# External_Power_Connectors.net
KiCad netlist of a schematic drawn in Altium Designer
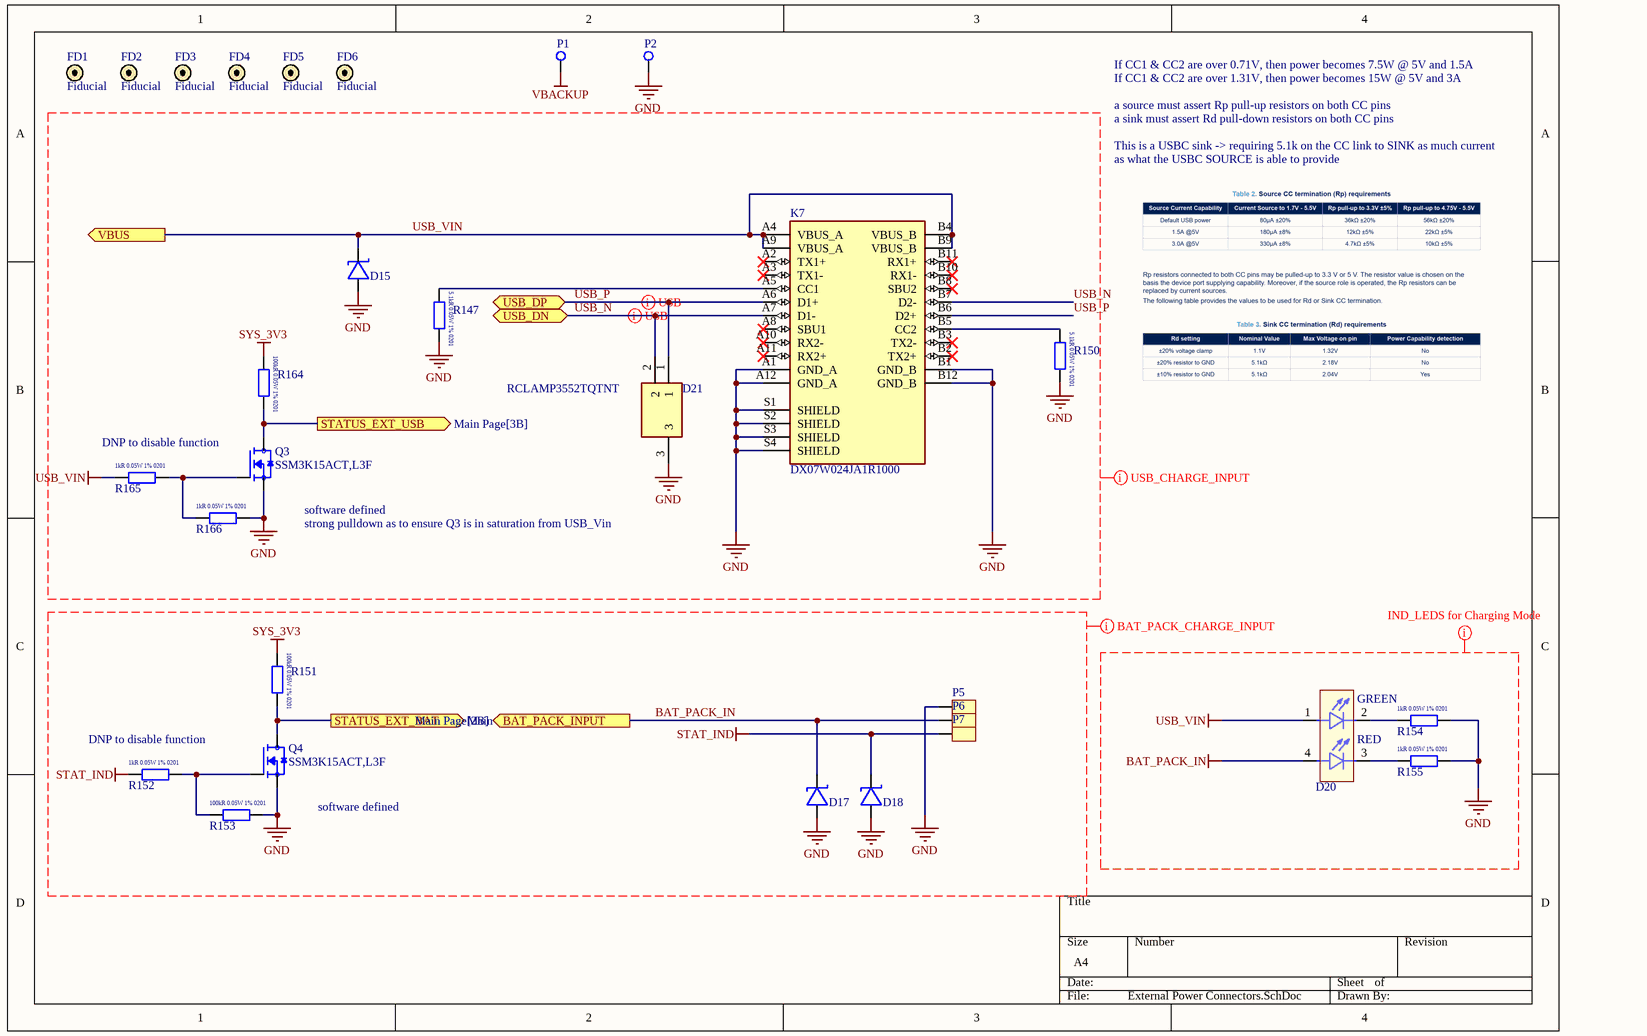
[diagram p0: External Power Connectors.SchDoc]

(export (version "E")
  (design (tool "Eeschema 10.0.6"))
  (components
    (comp (ref "D15")
      (value "RCLAMP04041PW.C")
      (footprint "RCLAMP04041PW.C")
      (description "8V Clamp 20A (8/20µs) Ipp Tvs Diode Surface Mount 2-DFN (1x0.6)")
      (libsource (lib "Gesturelink Schematic Library") (part "RCLAMP04041PW.C"))
    )
    (comp (ref "D17")
      (value "RCLAMP04041PW.C")
      (footprint "RCLAMP04041PW.C")
      (description "8V Clamp 20A (8/20µs) Ipp Tvs Diode Surface Mount 2-DFN (1x0.6)")
      (libsource (lib "Gesturelink Schematic Library") (part "RCLAMP04041PW.C"))
    )
    (comp (ref "D18")
      (value "RCLAMP04041PW.C")
      (footprint "RCLAMP04041PW.C")
      (description "8V Clamp 20A (8/20µs) Ipp Tvs Diode Surface Mount 2-DFN (1x0.6)")
      (libsource (lib "Gesturelink Schematic Library") (part "RCLAMP04041PW.C"))
    )
    (comp (ref "D20")
      (value "APGB0607G22R23C")
      (footprint "LED_APGB0607G22R23C")
      (description "Green, Red 525nm Green, 624nm Red LED Indication - Discrete 2.85V Green, 1.95V Red 4-SMD, No Lead")
      (libsource (lib "Gesturelink Schematic Library") (part "APGB0607G22R23C"))
    )
    (comp (ref "D21")
      (value "RCLAMP3552TQTNT")
      (footprint "SamacSys:RCLAMP3552TQTNT")
      (description "TVS Diode (Bi-directional)")
      (fields (field (name "MOUSER PART NUMBER") "947-RCLAMP3552TQTNT"))
      (libsource (lib "*") (part "RCLAMP3552TQTNT"))
    )
    (comp (ref "FD1")
      (value "Fiducial")
      (footprint "Fiducial")
      (libsource (lib "Gesturelink Schematic Library") (part "Fiducial"))
    )
    (comp (ref "FD2")
      (value "Fiducial")
      (footprint "Fiducial")
      (libsource (lib "Gesturelink Schematic Library") (part "Fiducial"))
    )
    (comp (ref "FD3")
      (value "Fiducial")
      (footprint "Fiducial")
      (libsource (lib "Gesturelink Schematic Library") (part "Fiducial"))
    )
    (comp (ref "FD4")
      (value "Fiducial")
      (footprint "Fiducial")
      (libsource (lib "Gesturelink Schematic Library") (part "Fiducial"))
    )
    (comp (ref "FD5")
      (value "Fiducial")
      (footprint "Fiducial")
      (libsource (lib "Gesturelink Schematic Library") (part "Fiducial"))
    )
    (comp (ref "FD6")
      (value "Fiducial")
      (footprint "Fiducial")
      (libsource (lib "Gesturelink Schematic Library") (part "Fiducial"))
    )
    (comp (ref "K7")
      (value "DX07W024JA1R1000")
      (footprint "JAE_DX07W024JA1R1000")
      (fields (field (name "MF") "JAE Electronics"))
      (libsource (lib "Gesturelink Schematic Library") (part "DX07W024JA1R1000"))
    )
    (comp (ref "P1")
      (value "Pogo pin Pad")
      (footprint "S70-220101045R")
      (description "Contact Spring Surface Mount")
      (libsource (lib "Gesturelink Schematic Library") (part "Pogo pin Pad"))
    )
    (comp (ref "P2")
      (value "Pogo pin Pad")
      (footprint "S70-220101045R")
      (description "Contact Spring Surface Mount")
      (libsource (lib "Gesturelink Schematic Library") (part "Pogo pin Pad"))
    )
    (comp (ref "P5")
      (value "Pad for Bat")
      (footprint "Pad for Bat")
      (libsource (lib "Gesturelink Schematic Library") (part "Pad for Bat"))
    )
    (comp (ref "P6")
      (value "Pad for Bat")
      (footprint "Pad for Bat")
      (libsource (lib "Gesturelink Schematic Library") (part "Pad for Bat"))
    )
    (comp (ref "P7")
      (value "Pad for Bat")
      (footprint "Pad for Bat")
      (libsource (lib "Gesturelink Schematic Library") (part "Pad for Bat"))
    )
    (comp (ref "Q3")
      (value "SSM3K15ACT,L3F")
      (footprint "SSM3K15ACT")
      (description "N-Channel 30 V 100mA (Ta) 100mW (Ta) Surface Mount CST3")
      (libsource (lib "Gesturelink Schematic Library") (part "SSM3K15ACT,L3F"))
    )
    (comp (ref "Q4")
      (value "SSM3K15ACT,L3F")
      (footprint "SSM3K15ACT")
      (description "N-Channel 30 V 100mA (Ta) 100mW (Ta) Surface Mount CST3")
      (libsource (lib "Gesturelink Schematic Library") (part "SSM3K15ACT,L3F"))
    )
    (comp (ref "R147")
      (value "ERJ-1GNF5101C")
      (footprint "RESC0603X03L")
      (description "5.1 kOhms ±1% 0.05W, 1/20W Chip Resistor 0201 (0603 Metric) Thick Film")
      (libsource (lib "Resistors") (part "ERJ-1GNF5101C"))
    )
    (comp (ref "R150")
      (value "ERJ-1GNF5101C")
      (footprint "RESC0603X03L")
      (description "5.1 kOhms ±1% 0.05W, 1/20W Chip Resistor 0201 (0603 Metric) Thick Film")
      (libsource (lib "Resistors") (part "ERJ-1GNF5101C"))
    )
    (comp (ref "R151")
      (value "ERJ-1GNF1003C")
      (footprint "RESC0603X03L")
      (description "100 kOhms ±1% 0.05W, 1/20W Chip Resistor 0201 (0603 Metric) Thick Film")
      (libsource (lib "Resistors") (part "ERJ-1GNF1003C"))
    )
    (comp (ref "R152")
      (value "ERJ-1GNF1001C")
      (footprint "RESC0603X03L")
      (description "1 kOhms ±1% 0.05W, 1/20W Chip Resistor 0201 (0603 Metric) Thick Film")
      (libsource (lib "Resistors") (part "ERJ-1GNF1001C"))
    )
    (comp (ref "R153")
      (value "ERJ-1GNF1003C")
      (footprint "RESC0603X03L")
      (description "100 kOhms ±1% 0.05W, 1/20W Chip Resistor 0201 (0603 Metric) Thick Film")
      (libsource (lib "") (part "ERJ-1GNF1003C_1"))
    )
    (comp (ref "R154")
      (value "ERJ-1GNF1001C")
      (footprint "RESC0603X03L")
      (description "1 kOhms ±1% 0.05W, 1/20W Chip Resistor 0201 (0603 Metric) Thick Film")
      (libsource (lib "Resistors") (part "ERJ-1GNF1001C"))
    )
    (comp (ref "R155")
      (value "ERJ-1GNF1001C")
      (footprint "RESC0603X03L")
      (description "1 kOhms ±1% 0.05W, 1/20W Chip Resistor 0201 (0603 Metric) Thick Film")
      (libsource (lib "Resistors") (part "ERJ-1GNF1001C"))
    )
    (comp (ref "R164")
      (value "ERJ-1GNF1003C")
      (footprint "RESC0603X03L")
      (description "100 kOhms ±1% 0.05W, 1/20W Chip Resistor 0201 (0603 Metric) Thick Film")
      (libsource (lib "Resistors") (part "ERJ-1GNF1003C"))
    )
    (comp (ref "R165")
      (value "ERJ-1GNF1001C")
      (footprint "RESC0603X03L")
      (description "1 kOhms ±1% 0.05W, 1/20W Chip Resistor 0201 (0603 Metric) Thick Film")
      (libsource (lib "Resistors") (part "ERJ-1GNF1001C"))
    )
    (comp (ref "R166")
      (value "ERJ-1GNF1001C")
      (footprint "RESC0603X03L")
      (description "1 kOhms ±1% 0.05W, 1/20W Chip Resistor 0201 (0603 Metric) Thick Film")
      (libsource (lib "Resistors") (part "ERJ-1GNF1001C"))
    )
  )
  (nets
    (net (code "1") (name "/STATUS_EXT_BAT") (class "Default")
      (node (ref "Q4") (pin "2") (pinfunction "D_2") (pintype "passive"))
      (node (ref "R151") (pin "2") (pinfunction "2_2") (pintype "passive"))
    )
    (net (code "2") (name "/STATUS_EXT_USB") (class "Default")
      (node (ref "Q3") (pin "2") (pinfunction "D_2") (pintype "passive"))
      (node (ref "R164") (pin "2") (pinfunction "2_2") (pintype "passive"))
    )
    (net (code "3") (name "/USB_N") (class "Default")
      (node (ref "D21") (pin "2") (pinfunction "2_2") (pintype "passive"))
      (node (ref "K7") (pin "A7") (pinfunction "D1-_A7") (pintype "bidirectional"))
      (node (ref "K7") (pin "B7") (pinfunction "D2-_B7") (pintype "bidirectional"))
    )
    (net (code "4") (name "/USB_P") (class "Default")
      (node (ref "D21") (pin "1") (pinfunction "1_1") (pintype "passive"))
      (node (ref "K7") (pin "A6") (pinfunction "D1+_A6") (pintype "bidirectional"))
      (node (ref "K7") (pin "B6") (pinfunction "D2+_B6") (pintype "bidirectional"))
    )
    (net (code "5") (name "BAT_PACK_IN") (class "Default")
      (node (ref "D17") (pin "2") (pinfunction "16_2") (pintype "passive"))
      (node (ref "D20") (pin "4") (pinfunction "A_RED_4") (pintype "passive"))
      (node (ref "P6") (pin "1") (pinfunction "1_1") (pintype "passive"))
    )
    (net (code "6") (name "GND") (class "Default")
      (node (ref "D15") (pin "1") (pinfunction "16_1") (pintype "passive"))
      (node (ref "D17") (pin "1") (pinfunction "16_1") (pintype "passive"))
      (node (ref "D18") (pin "1") (pinfunction "16_1") (pintype "passive"))
      (node (ref "D21") (pin "3") (pinfunction "3_3") (pintype "passive"))
      (node (ref "K7") (pin "A1") (pinfunction "GND_A_A1") (pintype "power_in"))
      (node (ref "K7") (pin "A12") (pinfunction "GND_A_A12") (pintype "power_in"))
      (node (ref "K7") (pin "B1") (pinfunction "GND_B_B1") (pintype "power_in"))
      (node (ref "K7") (pin "B12") (pinfunction "GND_B_B12") (pintype "power_in"))
      (node (ref "K7") (pin "S1") (pinfunction "SHIELD_S1") (pintype "passive"))
      (node (ref "K7") (pin "S2") (pinfunction "SHIELD_S2") (pintype "passive"))
      (node (ref "K7") (pin "S3") (pinfunction "SHIELD_S3") (pintype "passive"))
      (node (ref "K7") (pin "S4") (pinfunction "SHIELD_S4") (pintype "passive"))
      (node (ref "P2") (pin "1") (pinfunction "1_1") (pintype "passive"))
      (node (ref "P5") (pin "1") (pinfunction "1_1") (pintype "passive"))
      (node (ref "Q3") (pin "3") (pinfunction "S_3") (pintype "passive"))
      (node (ref "Q4") (pin "3") (pinfunction "S_3") (pintype "passive"))
      (node (ref "R147") (pin "2") (pinfunction "2_2") (pintype "passive"))
      (node (ref "R150") (pin "2") (pinfunction "2_2") (pintype "passive"))
      (node (ref "R153") (pin "2") (pinfunction "2_2") (pintype "passive"))
      (node (ref "R154") (pin "2") (pinfunction "2_2") (pintype "passive"))
      (node (ref "R155") (pin "2") (pinfunction "2_2") (pintype "passive"))
      (node (ref "R166") (pin "2") (pinfunction "2_2") (pintype "passive"))
    )
    (net (code "7") (name "Net-(D20-C_GREEN)") (class "Default")
      (node (ref "D20") (pin "2") (pinfunction "C_GREEN_2") (pintype "passive"))
      (node (ref "R154") (pin "1") (pinfunction "1_1") (pintype "passive"))
    )
    (net (code "8") (name "Net-(D20-C_RED)") (class "Default")
      (node (ref "D20") (pin "3") (pinfunction "C_RED_3") (pintype "passive"))
      (node (ref "R155") (pin "1") (pinfunction "1_1") (pintype "passive"))
    )
    (net (code "9") (name "Net-(K7-CC1)") (class "Default")
      (node (ref "K7") (pin "A5") (pinfunction "CC1_A5") (pintype "bidirectional"))
      (node (ref "R147") (pin "1") (pinfunction "1_1") (pintype "passive"))
    )
    (net (code "10") (name "Net-(K7-CC2)") (class "Default")
      (node (ref "K7") (pin "B5") (pinfunction "CC2_B5") (pintype "bidirectional"))
      (node (ref "R150") (pin "1") (pinfunction "1_1") (pintype "passive"))
    )
    (net (code "11") (name "Net-(Q3-G)") (class "Default")
      (node (ref "Q3") (pin "1") (pinfunction "G_1") (pintype "passive"))
      (node (ref "R165") (pin "2") (pinfunction "2_2") (pintype "passive"))
      (node (ref "R166") (pin "1") (pinfunction "1_1") (pintype "passive"))
    )
    (net (code "12") (name "Net-(Q4-G)") (class "Default")
      (node (ref "Q4") (pin "1") (pinfunction "G_1") (pintype "passive"))
      (node (ref "R152") (pin "2") (pinfunction "2_2") (pintype "passive"))
      (node (ref "R153") (pin "1") (pinfunction "1_1") (pintype "passive"))
    )
    (net (code "13") (name "STAT_IND") (class "Default")
      (node (ref "D18") (pin "2") (pinfunction "16_2") (pintype "passive"))
      (node (ref "P7") (pin "1") (pinfunction "1_1") (pintype "passive"))
      (node (ref "R152") (pin "1") (pinfunction "1_1") (pintype "passive"))
    )
    (net (code "14") (name "SYS_3V3") (class "Default")
      (node (ref "R151") (pin "1") (pinfunction "1_1") (pintype "passive"))
      (node (ref "R164") (pin "1") (pinfunction "1_1") (pintype "passive"))
    )
    (net (code "15") (name "USB_VIN") (class "Default")
      (node (ref "D15") (pin "2") (pinfunction "16_2") (pintype "passive"))
      (node (ref "D20") (pin "1") (pinfunction "A_GREEN_1") (pintype "passive"))
      (node (ref "K7") (pin "A4") (pinfunction "VBUS_A_A4") (pintype "power_in"))
      (node (ref "K7") (pin "A9") (pinfunction "VBUS_A_A9") (pintype "power_in"))
      (node (ref "K7") (pin "B4") (pinfunction "VBUS_B_B4") (pintype "power_in"))
      (node (ref "K7") (pin "B9") (pinfunction "VBUS_B_B9") (pintype "power_in"))
      (node (ref "R165") (pin "1") (pinfunction "1_1") (pintype "passive"))
    )
    (net (code "16") (name "VBACKUP") (class "Default")
      (node (ref "P1") (pin "1") (pinfunction "1_1") (pintype "passive"))
    )
    (net (code "17") (name "unconnected-(K7-RX1+-PadB11)") (class "Default")
      (node (ref "K7") (pin "B11") (pinfunction "RX1+_B11") (pintype "bidirectional+no_connect"))
    )
    (net (code "18") (name "unconnected-(K7-RX1--PadB10)") (class "Default")
      (node (ref "K7") (pin "B10") (pinfunction "RX1-_B10") (pintype "bidirectional+no_connect"))
    )
    (net (code "19") (name "unconnected-(K7-RX2+-PadA11)") (class "Default")
      (node (ref "K7") (pin "A11") (pinfunction "RX2+_A11") (pintype "bidirectional+no_connect"))
    )
    (net (code "20") (name "unconnected-(K7-RX2--PadA10)") (class "Default")
      (node (ref "K7") (pin "A10") (pinfunction "RX2-_A10") (pintype "bidirectional+no_connect"))
    )
    (net (code "21") (name "unconnected-(K7-SBU1-PadA8)") (class "Default")
      (node (ref "K7") (pin "A8") (pinfunction "SBU1_A8") (pintype "bidirectional+no_connect"))
    )
    (net (code "22") (name "unconnected-(K7-SBU2-PadB8)") (class "Default")
      (node (ref "K7") (pin "B8") (pinfunction "SBU2_B8") (pintype "bidirectional+no_connect"))
    )
    (net (code "23") (name "unconnected-(K7-TX1+-PadA2)") (class "Default")
      (node (ref "K7") (pin "A2") (pinfunction "TX1+_A2") (pintype "bidirectional+no_connect"))
    )
    (net (code "24") (name "unconnected-(K7-TX1--PadA3)") (class "Default")
      (node (ref "K7") (pin "A3") (pinfunction "TX1-_A3") (pintype "bidirectional+no_connect"))
    )
    (net (code "25") (name "unconnected-(K7-TX2+-PadB2)") (class "Default")
      (node (ref "K7") (pin "B2") (pinfunction "TX2+_B2") (pintype "bidirectional+no_connect"))
    )
    (net (code "26") (name "unconnected-(K7-TX2--PadB3)") (class "Default")
      (node (ref "K7") (pin "B3") (pinfunction "TX2-_B3") (pintype "bidirectional+no_connect"))
    )
  )
)
